# EITMUX.net
KiCad netlist of a schematic drawn in EAGLE
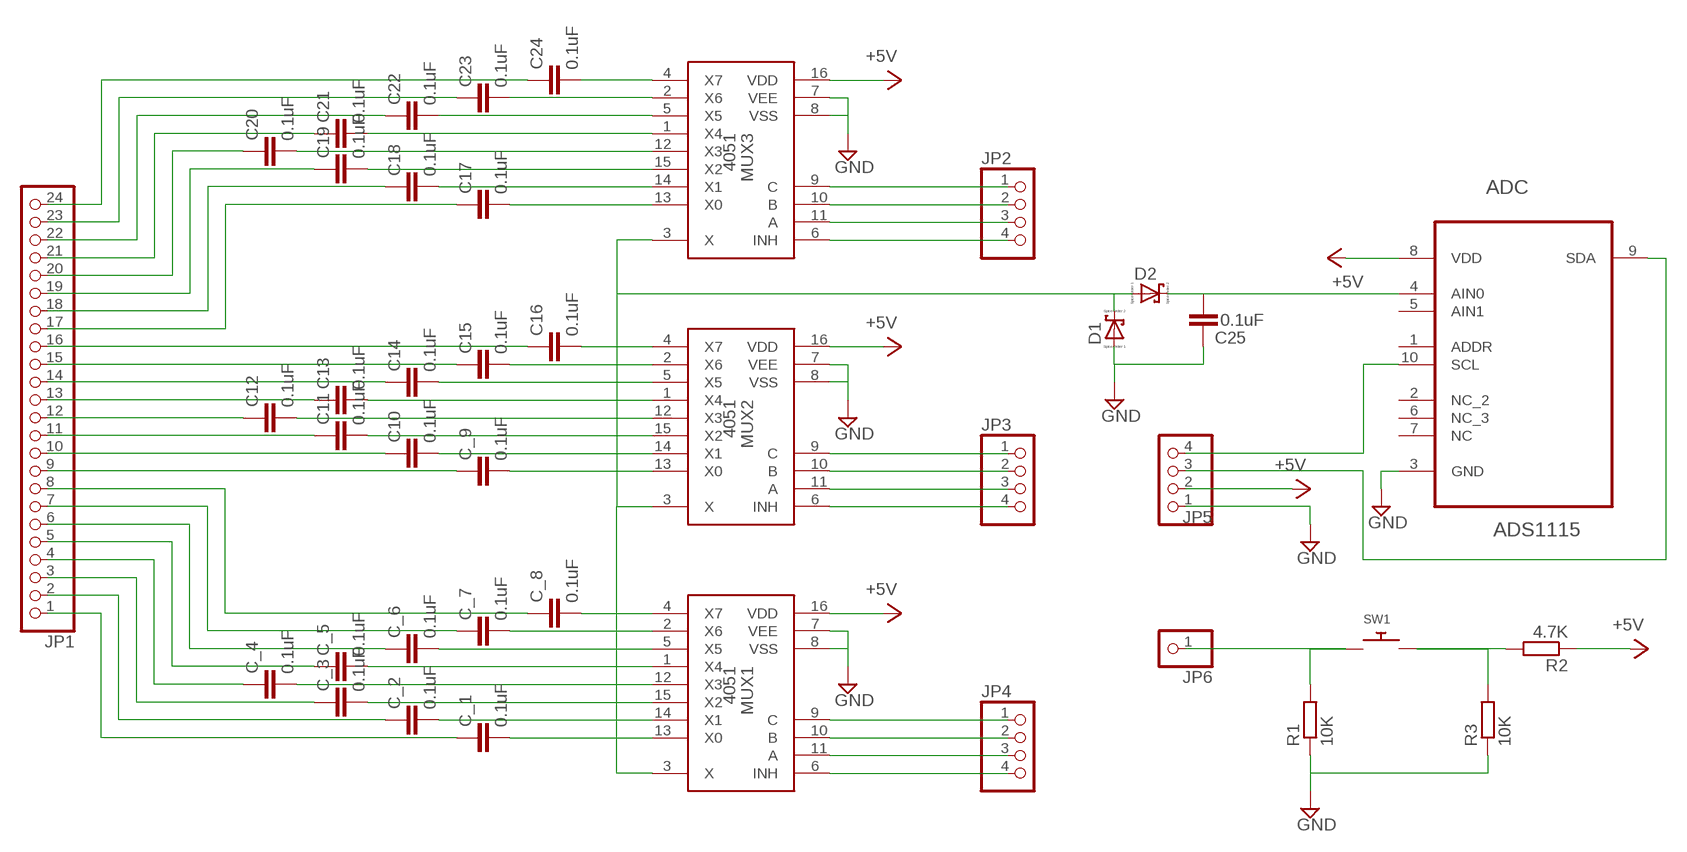
[diagram p0: schematic, sheet 1]

(export (version "E")
  (design (tool "Eeschema 10.0.6"))
  (components
    (comp (ref "ADC")
      (value "ADS1115")
      (footprint "eagle-import:SOP50P490X110-10N")
      (fields (field (name "MPN") "ADS1115IDGSR"))
      (libsource (lib "eagle-import") (part "ADS1115IDGSR"))
    )
    (comp (ref "C10")
      (value "0.1uF")
      (footprint "eagle-import:C0603")
      (libsource (lib "eagle-import") (part "C-EUC0603"))
    )
    (comp (ref "C11")
      (value "0.1uF")
      (footprint "eagle-import:C0603")
      (libsource (lib "eagle-import") (part "C-EUC0603"))
    )
    (comp (ref "C12")
      (value "0.1uF")
      (footprint "eagle-import:C0603")
      (libsource (lib "eagle-import") (part "C-EUC0603"))
    )
    (comp (ref "C13")
      (value "0.1uF")
      (footprint "eagle-import:C0603")
      (libsource (lib "eagle-import") (part "C-EUC0603"))
    )
    (comp (ref "C14")
      (value "0.1uF")
      (footprint "eagle-import:C0603")
      (libsource (lib "eagle-import") (part "C-EUC0603"))
    )
    (comp (ref "C15")
      (value "0.1uF")
      (footprint "eagle-import:C0603")
      (libsource (lib "eagle-import") (part "C-EUC0603"))
    )
    (comp (ref "C16")
      (value "0.1uF")
      (footprint "eagle-import:C0603")
      (libsource (lib "eagle-import") (part "C-EUC0603"))
    )
    (comp (ref "C17")
      (value "0.1uF")
      (footprint "eagle-import:C0603")
      (libsource (lib "eagle-import") (part "C-EUC0603"))
    )
    (comp (ref "C18")
      (value "0.1uF")
      (footprint "eagle-import:C0603")
      (libsource (lib "eagle-import") (part "C-EUC0603"))
    )
    (comp (ref "C19")
      (value "0.1uF")
      (footprint "eagle-import:C0603")
      (libsource (lib "eagle-import") (part "C-EUC0603"))
    )
    (comp (ref "C20")
      (value "0.1uF")
      (footprint "eagle-import:C0603")
      (libsource (lib "eagle-import") (part "C-EUC0603"))
    )
    (comp (ref "C21")
      (value "0.1uF")
      (footprint "eagle-import:C0603")
      (libsource (lib "eagle-import") (part "C-EUC0603"))
    )
    (comp (ref "C22")
      (value "0.1uF")
      (footprint "eagle-import:C0603")
      (libsource (lib "eagle-import") (part "C-EUC0603"))
    )
    (comp (ref "C23")
      (value "0.1uF")
      (footprint "eagle-import:C0603")
      (libsource (lib "eagle-import") (part "C-EUC0603"))
    )
    (comp (ref "C24")
      (value "0.1uF")
      (footprint "eagle-import:C0603")
      (libsource (lib "eagle-import") (part "C-EUC0603"))
    )
    (comp (ref "C25")
      (value "0.1uF")
      (footprint "eagle-import:C0603")
      (libsource (lib "eagle-import") (part "C-EUC0603"))
    )
    (comp (ref "C_1")
      (value "0.1uF")
      (footprint "eagle-import:C0603")
      (libsource (lib "eagle-import") (part "C-EUC0603"))
    )
    (comp (ref "C_2")
      (value "0.1uF")
      (footprint "eagle-import:C0603")
      (libsource (lib "eagle-import") (part "C-EUC0603"))
    )
    (comp (ref "C_3")
      (value "0.1uF")
      (footprint "eagle-import:C0603")
      (libsource (lib "eagle-import") (part "C-EUC0603"))
    )
    (comp (ref "C_4")
      (value "0.1uF")
      (footprint "eagle-import:C0603")
      (libsource (lib "eagle-import") (part "C-EUC0603"))
    )
    (comp (ref "C_5")
      (value "0.1uF")
      (footprint "eagle-import:C0603")
      (libsource (lib "eagle-import") (part "C-EUC0603"))
    )
    (comp (ref "C_6")
      (value "0.1uF")
      (footprint "eagle-import:C0603")
      (libsource (lib "eagle-import") (part "C-EUC0603"))
    )
    (comp (ref "C_7")
      (value "0.1uF")
      (footprint "eagle-import:C0603")
      (libsource (lib "eagle-import") (part "C-EUC0603"))
    )
    (comp (ref "C_8")
      (value "0.1uF")
      (footprint "eagle-import:C0603")
      (libsource (lib "eagle-import") (part "C-EUC0603"))
    )
    (comp (ref "C_9")
      (value "0.1uF")
      (footprint "eagle-import:C0603")
      (libsource (lib "eagle-import") (part "C-EUC0603"))
    )
    (comp (ref "D1")
      (value "SCHOTTKY-DIODEDO35-7")
      (footprint "eagle-import:DIODE_DO35-7")
      (libsource (lib "eagle-import") (part "SCHOTTKY-DIODEDO35-7"))
    )
    (comp (ref "D2")
      (value "SCHOTTKY-DIODEDO35-7")
      (footprint "eagle-import:DIODE_DO35-7")
      (libsource (lib "eagle-import") (part "SCHOTTKY-DIODEDO35-7"))
    )
    (comp (ref "JP1")
      (value "PINHD-1X24")
      (footprint "eagle-import:1X24")
      (libsource (lib "eagle-import") (part "PINHD-1X24"))
    )
    (comp (ref "JP2")
      (value "PINHD-1X4")
      (footprint "eagle-import:1X04")
      (libsource (lib "eagle-import") (part "PINHD-1X4"))
    )
    (comp (ref "JP3")
      (value "PINHD-1X4")
      (footprint "eagle-import:1X04")
      (libsource (lib "eagle-import") (part "PINHD-1X4"))
    )
    (comp (ref "JP4")
      (value "PINHD-1X4")
      (footprint "eagle-import:1X04")
      (libsource (lib "eagle-import") (part "PINHD-1X4"))
    )
    (comp (ref "JP5")
      (value "PINHD-1X4")
      (footprint "eagle-import:1X04")
      (libsource (lib "eagle-import") (part "PINHD-1X4"))
    )
    (comp (ref "JP6")
      (value "PINHD-1X1")
      (footprint "eagle-import:1X01")
      (libsource (lib "eagle-import") (part "PINHD-1X1"))
    )
    (comp (ref "MUX1")
      (value "4051")
      (footprint "eagle-import:DIL16")
      (libsource (lib "eagle-import") (part "4051JK"))
    )
    (comp (ref "MUX2")
      (value "4051")
      (footprint "eagle-import:DIL16")
      (libsource (lib "eagle-import") (part "4051JK"))
    )
    (comp (ref "MUX3")
      (value "4051")
      (footprint "eagle-import:DIL16")
      (libsource (lib "eagle-import") (part "4051JK"))
    )
    (comp (ref "R1")
      (value "10K")
      (footprint "eagle-import:R0603")
      (libsource (lib "eagle-import") (part "R-EU_R0603"))
    )
    (comp (ref "R2")
      (value "4.7K")
      (footprint "eagle-import:R0603")
      (libsource (lib "eagle-import") (part "R-EU_R0603"))
    )
    (comp (ref "R3")
      (value "10K")
      (footprint "eagle-import:R0603")
      (libsource (lib "eagle-import") (part "R-EU_R0603"))
    )
    (comp (ref "SW1")
      (value "SWITCH_PUSHBUTTONEVQ-PE")
      (footprint "eagle-import:TACT_PANA-EVQ")
      (libsource (lib "eagle-import") (part "SWITCH_PUSHBUTTONEVQ-PE"))
    )
  )
  (nets
    (net (code "1") (name "+5V") (class "Default")
      (node (ref "ADC") (pin "8") (pinfunction "VDD_8") (pintype "power_in"))
      (node (ref "JP5") (pin "2") (pinfunction "2_2") (pintype "passive"))
      (node (ref "MUX1") (pin "16") (pinfunction "VDD_16") (pintype "input"))
      (node (ref "MUX2") (pin "16") (pinfunction "VDD_16") (pintype "input"))
      (node (ref "MUX3") (pin "16") (pinfunction "VDD_16") (pintype "input"))
      (node (ref "R2") (pin "1") (pinfunction "1_1") (pintype "passive"))
    )
    (net (code "2") (name "GND") (class "Default")
      (node (ref "ADC") (pin "3") (pinfunction "GND_3") (pintype "passive"))
      (node (ref "C25") (pin "1") (pinfunction "1_1") (pintype "passive"))
      (node (ref "D1") (pin "A") (pinfunction "C_A") (pintype "passive"))
      (node (ref "JP5") (pin "1") (pinfunction "1_1") (pintype "passive"))
      (node (ref "MUX1") (pin "7") (pinfunction "VEE_7") (pintype "input"))
      (node (ref "MUX1") (pin "8") (pinfunction "VSS_8") (pintype "input"))
      (node (ref "MUX2") (pin "7") (pinfunction "VEE_7") (pintype "input"))
      (node (ref "MUX2") (pin "8") (pinfunction "VSS_8") (pintype "input"))
      (node (ref "MUX3") (pin "7") (pinfunction "VEE_7") (pintype "input"))
      (node (ref "MUX3") (pin "8") (pinfunction "VSS_8") (pintype "input"))
      (node (ref "R1") (pin "1") (pinfunction "1_1") (pintype "passive"))
      (node (ref "R3") (pin "1") (pinfunction "1_1") (pintype "passive"))
    )
    (net (code "3") (name "Net-(ADC-AIN0)") (class "Default")
      (node (ref "ADC") (pin "4") (pinfunction "AIN0_4") (pintype "input"))
      (node (ref "C25") (pin "2") (pinfunction "2_2") (pintype "passive"))
      (node (ref "D2") (pin "C") (pinfunction "A_C") (pintype "passive"))
    )
    (net (code "4") (name "Net-(ADC-SCL)") (class "Default")
      (node (ref "ADC") (pin "10") (pinfunction "SCL_10") (pintype "input"))
      (node (ref "JP5") (pin "4") (pinfunction "4_4") (pintype "passive"))
    )
    (net (code "5") (name "Net-(ADC-SDA)") (class "Default")
      (node (ref "ADC") (pin "9") (pinfunction "SDA_9") (pintype "bidirectional"))
      (node (ref "JP5") (pin "3") (pinfunction "3_3") (pintype "passive"))
    )
    (net (code "6") (name "Net-(C10-Pad1)") (class "Default")
      (node (ref "C10") (pin "1") (pinfunction "1_1") (pintype "passive"))
      (node (ref "JP1") (pin "10") (pinfunction "10_10") (pintype "passive"))
    )
    (net (code "7") (name "Net-(C11-Pad1)") (class "Default")
      (node (ref "C11") (pin "1") (pinfunction "1_1") (pintype "passive"))
      (node (ref "JP1") (pin "11") (pinfunction "11_11") (pintype "passive"))
    )
    (net (code "8") (name "Net-(C12-Pad1)") (class "Default")
      (node (ref "C12") (pin "1") (pinfunction "1_1") (pintype "passive"))
      (node (ref "JP1") (pin "12") (pinfunction "12_12") (pintype "passive"))
    )
    (net (code "9") (name "Net-(C13-Pad1)") (class "Default")
      (node (ref "C13") (pin "1") (pinfunction "1_1") (pintype "passive"))
      (node (ref "JP1") (pin "13") (pinfunction "13_13") (pintype "passive"))
    )
    (net (code "10") (name "Net-(C14-Pad1)") (class "Default")
      (node (ref "C14") (pin "1") (pinfunction "1_1") (pintype "passive"))
      (node (ref "JP1") (pin "14") (pinfunction "14_14") (pintype "passive"))
    )
    (net (code "11") (name "Net-(C15-Pad1)") (class "Default")
      (node (ref "C15") (pin "1") (pinfunction "1_1") (pintype "passive"))
      (node (ref "JP1") (pin "15") (pinfunction "15_15") (pintype "passive"))
    )
    (net (code "12") (name "Net-(C16-Pad1)") (class "Default")
      (node (ref "C16") (pin "1") (pinfunction "1_1") (pintype "passive"))
      (node (ref "JP1") (pin "16") (pinfunction "16_16") (pintype "passive"))
    )
    (net (code "13") (name "Net-(C17-Pad1)") (class "Default")
      (node (ref "C17") (pin "1") (pinfunction "1_1") (pintype "passive"))
      (node (ref "JP1") (pin "17") (pinfunction "17_17") (pintype "passive"))
    )
    (net (code "14") (name "Net-(C18-Pad1)") (class "Default")
      (node (ref "C18") (pin "1") (pinfunction "1_1") (pintype "passive"))
      (node (ref "JP1") (pin "18") (pinfunction "18_18") (pintype "passive"))
    )
    (net (code "15") (name "Net-(C19-Pad1)") (class "Default")
      (node (ref "C19") (pin "1") (pinfunction "1_1") (pintype "passive"))
      (node (ref "JP1") (pin "19") (pinfunction "19_19") (pintype "passive"))
    )
    (net (code "16") (name "Net-(C20-Pad1)") (class "Default")
      (node (ref "C20") (pin "1") (pinfunction "1_1") (pintype "passive"))
      (node (ref "JP1") (pin "20") (pinfunction "20_20") (pintype "passive"))
    )
    (net (code "17") (name "Net-(C21-Pad1)") (class "Default")
      (node (ref "C21") (pin "1") (pinfunction "1_1") (pintype "passive"))
      (node (ref "JP1") (pin "21") (pinfunction "21_21") (pintype "passive"))
    )
    (net (code "18") (name "Net-(C22-Pad1)") (class "Default")
      (node (ref "C22") (pin "1") (pinfunction "1_1") (pintype "passive"))
      (node (ref "JP1") (pin "22") (pinfunction "22_22") (pintype "passive"))
    )
    (net (code "19") (name "Net-(C23-Pad1)") (class "Default")
      (node (ref "C23") (pin "1") (pinfunction "1_1") (pintype "passive"))
      (node (ref "JP1") (pin "23") (pinfunction "23_23") (pintype "passive"))
    )
    (net (code "20") (name "Net-(C24-Pad1)") (class "Default")
      (node (ref "C24") (pin "1") (pinfunction "1_1") (pintype "passive"))
      (node (ref "JP1") (pin "24") (pinfunction "24_24") (pintype "passive"))
    )
    (net (code "21") (name "Net-(C_1-Pad1)") (class "Default")
      (node (ref "C_1") (pin "1") (pinfunction "1_1") (pintype "passive"))
      (node (ref "JP1") (pin "1") (pinfunction "1_1") (pintype "passive"))
    )
    (net (code "22") (name "Net-(C_2-Pad1)") (class "Default")
      (node (ref "C_2") (pin "1") (pinfunction "1_1") (pintype "passive"))
      (node (ref "JP1") (pin "2") (pinfunction "2_2") (pintype "passive"))
    )
    (net (code "23") (name "Net-(C_3-Pad1)") (class "Default")
      (node (ref "C_3") (pin "1") (pinfunction "1_1") (pintype "passive"))
      (node (ref "JP1") (pin "3") (pinfunction "3_3") (pintype "passive"))
    )
    (net (code "24") (name "Net-(C_4-Pad1)") (class "Default")
      (node (ref "C_4") (pin "1") (pinfunction "1_1") (pintype "passive"))
      (node (ref "JP1") (pin "4") (pinfunction "4_4") (pintype "passive"))
    )
    (net (code "25") (name "Net-(C_5-Pad1)") (class "Default")
      (node (ref "C_5") (pin "1") (pinfunction "1_1") (pintype "passive"))
      (node (ref "JP1") (pin "5") (pinfunction "5_5") (pintype "passive"))
    )
    (net (code "26") (name "Net-(C_6-Pad1)") (class "Default")
      (node (ref "C_6") (pin "1") (pinfunction "1_1") (pintype "passive"))
      (node (ref "JP1") (pin "6") (pinfunction "6_6") (pintype "passive"))
    )
    (net (code "27") (name "Net-(C_7-Pad1)") (class "Default")
      (node (ref "C_7") (pin "1") (pinfunction "1_1") (pintype "passive"))
      (node (ref "JP1") (pin "7") (pinfunction "7_7") (pintype "passive"))
    )
    (net (code "28") (name "Net-(C_8-Pad1)") (class "Default")
      (node (ref "C_8") (pin "1") (pinfunction "1_1") (pintype "passive"))
      (node (ref "JP1") (pin "8") (pinfunction "8_8") (pintype "passive"))
    )
    (net (code "29") (name "Net-(C_9-Pad1)") (class "Default")
      (node (ref "C_9") (pin "1") (pinfunction "1_1") (pintype "passive"))
      (node (ref "JP1") (pin "9") (pinfunction "9_9") (pintype "passive"))
    )
    (net (code "30") (name "Net-(D1-A)") (class "Default")
      (node (ref "D1") (pin "C") (pinfunction "A_C") (pintype "passive"))
      (node (ref "D2") (pin "A") (pinfunction "C_A") (pintype "passive"))
      (node (ref "MUX1") (pin "3") (pinfunction "X_3") (pintype "bidirectional"))
      (node (ref "MUX2") (pin "3") (pinfunction "X_3") (pintype "bidirectional"))
      (node (ref "MUX3") (pin "3") (pinfunction "X_3") (pintype "bidirectional"))
    )
    (net (code "31") (name "Net-(JP6-Pad1)") (class "Default")
      (node (ref "JP6") (pin "1") (pinfunction "1_1") (pintype "passive"))
      (node (ref "R1") (pin "2") (pinfunction "2_2") (pintype "passive"))
      (node (ref "SW1") (pin "P$1") (pinfunction "P$1_P$1") (pintype "passive"))
    )
    (net (code "32") (name "Net-(MUX1-A)") (class "Default")
      (node (ref "JP4") (pin "3") (pinfunction "3_3") (pintype "passive"))
      (node (ref "MUX1") (pin "11") (pinfunction "A_11") (pintype "input"))
    )
    (net (code "33") (name "Net-(MUX1-B)") (class "Default")
      (node (ref "JP4") (pin "2") (pinfunction "2_2") (pintype "passive"))
      (node (ref "MUX1") (pin "10") (pinfunction "B_10") (pintype "input"))
    )
    (net (code "34") (name "Net-(MUX1-C)") (class "Default")
      (node (ref "JP4") (pin "1") (pinfunction "1_1") (pintype "passive"))
      (node (ref "MUX1") (pin "9") (pinfunction "C_9") (pintype "input"))
    )
    (net (code "35") (name "Net-(MUX1-INH)") (class "Default")
      (node (ref "JP4") (pin "4") (pinfunction "4_4") (pintype "passive"))
      (node (ref "MUX1") (pin "6") (pinfunction "INH_6") (pintype "input"))
    )
    (net (code "36") (name "Net-(MUX1-X0)") (class "Default")
      (node (ref "C_1") (pin "2") (pinfunction "2_2") (pintype "passive"))
      (node (ref "MUX1") (pin "13") (pinfunction "X0_13") (pintype "bidirectional"))
    )
    (net (code "37") (name "Net-(MUX1-X1)") (class "Default")
      (node (ref "C_2") (pin "2") (pinfunction "2_2") (pintype "passive"))
      (node (ref "MUX1") (pin "14") (pinfunction "X1_14") (pintype "bidirectional"))
    )
    (net (code "38") (name "Net-(MUX1-X2)") (class "Default")
      (node (ref "C_3") (pin "2") (pinfunction "2_2") (pintype "passive"))
      (node (ref "MUX1") (pin "15") (pinfunction "X2_15") (pintype "bidirectional"))
    )
    (net (code "39") (name "Net-(MUX1-X3)") (class "Default")
      (node (ref "C_4") (pin "2") (pinfunction "2_2") (pintype "passive"))
      (node (ref "MUX1") (pin "12") (pinfunction "X3_12") (pintype "bidirectional"))
    )
    (net (code "40") (name "Net-(MUX1-X4)") (class "Default")
      (node (ref "C_5") (pin "2") (pinfunction "2_2") (pintype "passive"))
      (node (ref "MUX1") (pin "1") (pinfunction "X4_1") (pintype "bidirectional"))
    )
    (net (code "41") (name "Net-(MUX1-X5)") (class "Default")
      (node (ref "C_6") (pin "2") (pinfunction "2_2") (pintype "passive"))
      (node (ref "MUX1") (pin "5") (pinfunction "X5_5") (pintype "bidirectional"))
    )
    (net (code "42") (name "Net-(MUX1-X6)") (class "Default")
      (node (ref "C_7") (pin "2") (pinfunction "2_2") (pintype "passive"))
      (node (ref "MUX1") (pin "2") (pinfunction "X6_2") (pintype "bidirectional"))
    )
    (net (code "43") (name "Net-(MUX1-X7)") (class "Default")
      (node (ref "C_8") (pin "2") (pinfunction "2_2") (pintype "passive"))
      (node (ref "MUX1") (pin "4") (pinfunction "X7_4") (pintype "bidirectional"))
    )
    (net (code "44") (name "Net-(MUX2-A)") (class "Default")
      (node (ref "JP3") (pin "3") (pinfunction "3_3") (pintype "passive"))
      (node (ref "MUX2") (pin "11") (pinfunction "A_11") (pintype "input"))
    )
    (net (code "45") (name "Net-(MUX2-B)") (class "Default")
      (node (ref "JP3") (pin "2") (pinfunction "2_2") (pintype "passive"))
      (node (ref "MUX2") (pin "10") (pinfunction "B_10") (pintype "input"))
    )
    (net (code "46") (name "Net-(MUX2-C)") (class "Default")
      (node (ref "JP3") (pin "1") (pinfunction "1_1") (pintype "passive"))
      (node (ref "MUX2") (pin "9") (pinfunction "C_9") (pintype "input"))
    )
    (net (code "47") (name "Net-(MUX2-INH)") (class "Default")
      (node (ref "JP3") (pin "4") (pinfunction "4_4") (pintype "passive"))
      (node (ref "MUX2") (pin "6") (pinfunction "INH_6") (pintype "input"))
    )
    (net (code "48") (name "Net-(MUX2-X0)") (class "Default")
      (node (ref "C_9") (pin "2") (pinfunction "2_2") (pintype "passive"))
      (node (ref "MUX2") (pin "13") (pinfunction "X0_13") (pintype "bidirectional"))
    )
    (net (code "49") (name "Net-(MUX2-X1)") (class "Default")
      (node (ref "C10") (pin "2") (pinfunction "2_2") (pintype "passive"))
      (node (ref "MUX2") (pin "14") (pinfunction "X1_14") (pintype "bidirectional"))
    )
    (net (code "50") (name "Net-(MUX2-X2)") (class "Default")
      (node (ref "C11") (pin "2") (pinfunction "2_2") (pintype "passive"))
      (node (ref "MUX2") (pin "15") (pinfunction "X2_15") (pintype "bidirectional"))
    )
    (net (code "51") (name "Net-(MUX2-X3)") (class "Default")
      (node (ref "C12") (pin "2") (pinfunction "2_2") (pintype "passive"))
      (node (ref "MUX2") (pin "12") (pinfunction "X3_12") (pintype "bidirectional"))
    )
    (net (code "52") (name "Net-(MUX2-X4)") (class "Default")
      (node (ref "C13") (pin "2") (pinfunction "2_2") (pintype "passive"))
      (node (ref "MUX2") (pin "1") (pinfunction "X4_1") (pintype "bidirectional"))
    )
    (net (code "53") (name "Net-(MUX2-X5)") (class "Default")
      (node (ref "C14") (pin "2") (pinfunction "2_2") (pintype "passive"))
      (node (ref "MUX2") (pin "5") (pinfunction "X5_5") (pintype "bidirectional"))
    )
    (net (code "54") (name "Net-(MUX2-X6)") (class "Default")
      (node (ref "C15") (pin "2") (pinfunction "2_2") (pintype "passive"))
      (node (ref "MUX2") (pin "2") (pinfunction "X6_2") (pintype "bidirectional"))
    )
    (net (code "55") (name "Net-(MUX2-X7)") (class "Default")
      (node (ref "C16") (pin "2") (pinfunction "2_2") (pintype "passive"))
      (node (ref "MUX2") (pin "4") (pinfunction "X7_4") (pintype "bidirectional"))
    )
    (net (code "56") (name "Net-(MUX3-A)") (class "Default")
      (node (ref "JP2") (pin "3") (pinfunction "3_3") (pintype "passive"))
      (node (ref "MUX3") (pin "11") (pinfunction "A_11") (pintype "input"))
    )
    (net (code "57") (name "Net-(MUX3-B)") (class "Default")
      (node (ref "JP2") (pin "2") (pinfunction "2_2") (pintype "passive"))
      (node (ref "MUX3") (pin "10") (pinfunction "B_10") (pintype "input"))
    )
    (net (code "58") (name "Net-(MUX3-C)") (class "Default")
      (node (ref "JP2") (pin "1") (pinfunction "1_1") (pintype "passive"))
      (node (ref "MUX3") (pin "9") (pinfunction "C_9") (pintype "input"))
    )
    (net (code "59") (name "Net-(MUX3-INH)") (class "Default")
      (node (ref "JP2") (pin "4") (pinfunction "4_4") (pintype "passive"))
      (node (ref "MUX3") (pin "6") (pinfunction "INH_6") (pintype "input"))
    )
    (net (code "60") (name "Net-(MUX3-X0)") (class "Default")
      (node (ref "C17") (pin "2") (pinfunction "2_2") (pintype "passive"))
      (node (ref "MUX3") (pin "13") (pinfunction "X0_13") (pintype "bidirectional"))
    )
    (net (code "61") (name "Net-(MUX3-X1)") (class "Default")
      (node (ref "C18") (pin "2") (pinfunction "2_2") (pintype "passive"))
      (node (ref "MUX3") (pin "14") (pinfunction "X1_14") (pintype "bidirectional"))
    )
    (net (code "62") (name "Net-(MUX3-X2)") (class "Default")
      (node (ref "C19") (pin "2") (pinfunction "2_2") (pintype "passive"))
      (node (ref "MUX3") (pin "15") (pinfunction "X2_15") (pintype "bidirectional"))
    )
    (net (code "63") (name "Net-(MUX3-X3)") (class "Default")
      (node (ref "C20") (pin "2") (pinfunction "2_2") (pintype "passive"))
      (node (ref "MUX3") (pin "12") (pinfunction "X3_12") (pintype "bidirectional"))
    )
    (net (code "64") (name "Net-(MUX3-X4)") (class "Default")
      (node (ref "C21") (pin "2") (pinfunction "2_2") (pintype "passive"))
      (node (ref "MUX3") (pin "1") (pinfunction "X4_1") (pintype "bidirectional"))
    )
    (net (code "65") (name "Net-(MUX3-X5)") (class "Default")
      (node (ref "C22") (pin "2") (pinfunction "2_2") (pintype "passive"))
      (node (ref "MUX3") (pin "5") (pinfunction "X5_5") (pintype "bidirectional"))
    )
    (net (code "66") (name "Net-(MUX3-X6)") (class "Default")
      (node (ref "C23") (pin "2") (pinfunction "2_2") (pintype "passive"))
      (node (ref "MUX3") (pin "2") (pinfunction "X6_2") (pintype "bidirectional"))
    )
    (net (code "67") (name "Net-(MUX3-X7)") (class "Default")
      (node (ref "C24") (pin "2") (pinfunction "2_2") (pintype "passive"))
      (node (ref "MUX3") (pin "4") (pinfunction "X7_4") (pintype "bidirectional"))
    )
    (net (code "68") (name "Net-(R2-Pad2)") (class "Default")
      (node (ref "R2") (pin "2") (pinfunction "2_2") (pintype "passive"))
      (node (ref "R3") (pin "2") (pinfunction "2_2") (pintype "passive"))
      (node (ref "SW1") (pin "P$2") (pinfunction "P$2_P$2") (pintype "passive"))
    )
    (net (code "69") (name "unconnected-(ADC-ADDR-Pad1)") (class "Default")
      (node (ref "ADC") (pin "1") (pinfunction "ADDR_1") (pintype "input"))
    )
    (net (code "70") (name "unconnected-(ADC-AIN1-Pad5)") (class "Default")
      (node (ref "ADC") (pin "5") (pinfunction "AIN1_5") (pintype "input"))
    )
    (net (code "71") (name "unconnected-(ADC-NC-Pad7)") (class "Default")
      (node (ref "ADC") (pin "7") (pinfunction "NC_7") (pintype "no_connect"))
    )
    (net (code "72") (name "unconnected-(ADC-NC_2-Pad2)") (class "Default")
      (node (ref "ADC") (pin "2") (pinfunction "NC_2_2") (pintype "no_connect"))
    )
    (net (code "73") (name "unconnected-(ADC-NC_3-Pad6)") (class "Default")
      (node (ref "ADC") (pin "6") (pinfunction "NC_3_6") (pintype "no_connect"))
    )
  )
)
